# EXT_TMC222.net
KiCad netlist of a schematic drawn in EAGLE
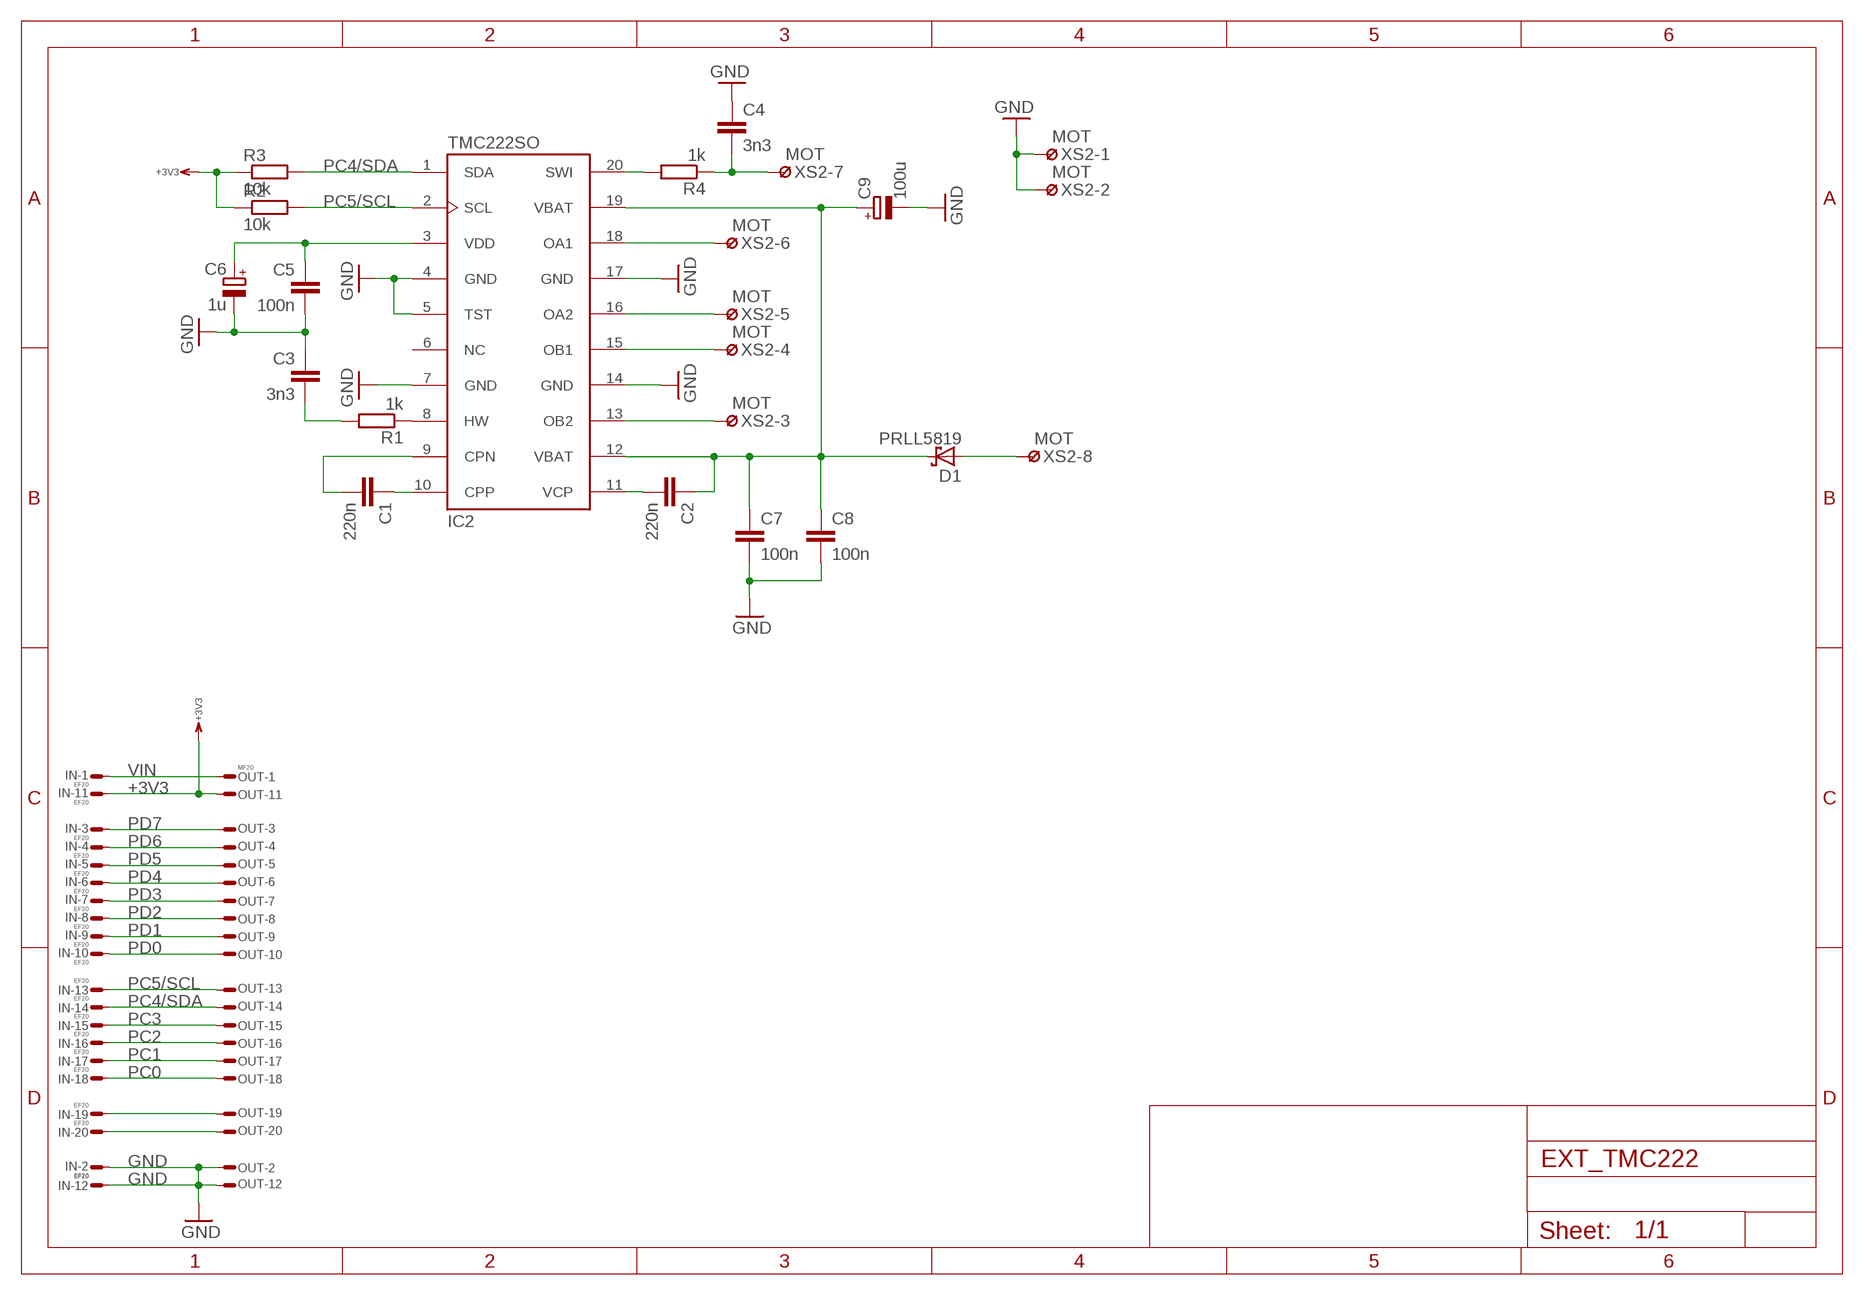
[diagram p0: schematic, sheet 1]

(export (version "E")
  (design (tool "Eeschema 10.0.6"))
  (components
    (comp (ref "C1")
      (value "220n")
      (footprint "eagle-import:1206")
      (libsource (lib "eagle-import") (part "C1206"))
    )
    (comp (ref "C2")
      (value "220n")
      (footprint "eagle-import:1206")
      (libsource (lib "eagle-import") (part "C1206"))
    )
    (comp (ref "C3")
      (value "3n3")
      (footprint "eagle-import:0603")
      (libsource (lib "eagle-import") (part "C0603"))
    )
    (comp (ref "C4")
      (value "3n3")
      (footprint "eagle-import:0603")
      (libsource (lib "eagle-import") (part "C0603"))
    )
    (comp (ref "C5")
      (value "100n")
      (footprint "eagle-import:0603")
      (libsource (lib "eagle-import") (part "C0603"))
    )
    (comp (ref "C6")
      (value "1u")
      (footprint "eagle-import:SMC_A")
      (libsource (lib "eagle-import") (part "C_POLSMCA"))
    )
    (comp (ref "C7")
      (value "100n")
      (footprint "eagle-import:1206")
      (libsource (lib "eagle-import") (part "C1206"))
    )
    (comp (ref "C8")
      (value "100n")
      (footprint "eagle-import:1206")
      (libsource (lib "eagle-import") (part "C1206"))
    )
    (comp (ref "C9")
      (value "100u")
      (footprint "eagle-import:E3,5-8")
      (libsource (lib "eagle-import") (part "C_POLE3.5-8"))
    )
    (comp (ref "D1")
      (value "PRLL5819")
      (footprint "eagle-import:SOD87")
      (libsource (lib "eagle-import") (part "D-SCHOTKY7"))
    )
    (comp (ref "IC2")
      (value "TMC222SO")
      (footprint "eagle-import:SOIC20")
      (libsource (lib "eagle-import") (part "TMC222SO"))
    )
    (comp (ref "IN")
      (value "EF20")
      (footprint "eagle-import:FE10-2WSS")
      (libsource (lib "eagle-import") (part "FE20ELSS"))
    )
    (comp (ref "OUT")
      (value "MF20")
      (footprint "eagle-import:ML20LS")
      (libsource (lib "eagle-import") (part "ML20?ELS"))
    )
    (comp (ref "R1")
      (value "1k")
      (footprint "eagle-import:0603")
      (libsource (lib "eagle-import") (part "R0603"))
    )
    (comp (ref "R2")
      (value "10k")
      (footprint "eagle-import:0603")
      (libsource (lib "eagle-import") (part "R0603"))
    )
    (comp (ref "R3")
      (value "10k")
      (footprint "eagle-import:0603")
      (libsource (lib "eagle-import") (part "R0603"))
    )
    (comp (ref "R4")
      (value "1k")
      (footprint "eagle-import:0603")
      (libsource (lib "eagle-import") (part "R0603"))
    )
    (comp (ref "XS2")
      (value "MOT")
      (footprint "eagle-import:1727078")
      (libsource (lib "eagle-import") (part "CON8-SS381"))
    )
  )
  (nets
    (net (code "1") (name "+3V3") (class "Default")
      (node (ref "IN") (pin "P$11") (pinfunction "S_P$11") (pintype "passive"))
      (node (ref "OUT") (pin "P$11") (pinfunction "S_P$11") (pintype "passive"))
      (node (ref "R2") (pin "1") (pinfunction "1_1") (pintype "passive"))
      (node (ref "R3") (pin "1") (pinfunction "1_1") (pintype "passive"))
    )
    (net (code "2") (name "/PC0") (class "Default")
      (node (ref "IN") (pin "P$18") (pinfunction "S_P$18") (pintype "passive"))
      (node (ref "OUT") (pin "P$18") (pinfunction "S_P$18") (pintype "passive"))
    )
    (net (code "3") (name "/PC1") (class "Default")
      (node (ref "IN") (pin "P$17") (pinfunction "S_P$17") (pintype "passive"))
      (node (ref "OUT") (pin "P$17") (pinfunction "S_P$17") (pintype "passive"))
    )
    (net (code "4") (name "/PC2") (class "Default")
      (node (ref "IN") (pin "P$16") (pinfunction "S_P$16") (pintype "passive"))
      (node (ref "OUT") (pin "P$16") (pinfunction "S_P$16") (pintype "passive"))
    )
    (net (code "5") (name "/PC3") (class "Default")
      (node (ref "IN") (pin "P$15") (pinfunction "S_P$15") (pintype "passive"))
      (node (ref "OUT") (pin "P$15") (pinfunction "S_P$15") (pintype "passive"))
    )
    (net (code "6") (name "/PC4{slash}SDA") (class "Default")
      (node (ref "IC2") (pin "1") (pinfunction "SDA_1") (pintype "bidirectional"))
      (node (ref "IN") (pin "P$14") (pinfunction "S_P$14") (pintype "passive"))
      (node (ref "OUT") (pin "P$14") (pinfunction "S_P$14") (pintype "passive"))
      (node (ref "R3") (pin "2") (pinfunction "2_2") (pintype "passive"))
    )
    (net (code "7") (name "/PC5{slash}SCL") (class "Default")
      (node (ref "IC2") (pin "2") (pinfunction "SCL_2") (pintype "bidirectional"))
      (node (ref "IN") (pin "P$13") (pinfunction "S_P$13") (pintype "passive"))
      (node (ref "OUT") (pin "P$13") (pinfunction "S_P$13") (pintype "passive"))
      (node (ref "R2") (pin "2") (pinfunction "2_2") (pintype "passive"))
    )
    (net (code "8") (name "/PD0") (class "Default")
      (node (ref "IN") (pin "P$10") (pinfunction "S_P$10") (pintype "passive"))
      (node (ref "OUT") (pin "P$10") (pinfunction "S_P$10") (pintype "passive"))
    )
    (net (code "9") (name "/PD1") (class "Default")
      (node (ref "IN") (pin "P$9") (pinfunction "S_P$9") (pintype "passive"))
      (node (ref "OUT") (pin "P$9") (pinfunction "S_P$9") (pintype "passive"))
    )
    (net (code "10") (name "/PD2") (class "Default")
      (node (ref "IN") (pin "P$8") (pinfunction "S_P$8") (pintype "passive"))
      (node (ref "OUT") (pin "P$8") (pinfunction "S_P$8") (pintype "passive"))
    )
    (net (code "11") (name "/PD3") (class "Default")
      (node (ref "IN") (pin "P$7") (pinfunction "S_P$7") (pintype "passive"))
      (node (ref "OUT") (pin "P$7") (pinfunction "S_P$7") (pintype "passive"))
    )
    (net (code "12") (name "/PD4") (class "Default")
      (node (ref "IN") (pin "P$6") (pinfunction "S_P$6") (pintype "passive"))
      (node (ref "OUT") (pin "P$6") (pinfunction "S_P$6") (pintype "passive"))
    )
    (net (code "13") (name "/PD5") (class "Default")
      (node (ref "IN") (pin "P$5") (pinfunction "S_P$5") (pintype "passive"))
      (node (ref "OUT") (pin "P$5") (pinfunction "S_P$5") (pintype "passive"))
    )
    (net (code "14") (name "/PD6") (class "Default")
      (node (ref "IN") (pin "P$4") (pinfunction "S_P$4") (pintype "passive"))
      (node (ref "OUT") (pin "P$4") (pinfunction "S_P$4") (pintype "passive"))
    )
    (net (code "15") (name "/PD7") (class "Default")
      (node (ref "IN") (pin "P$3") (pinfunction "S_P$3") (pintype "passive"))
      (node (ref "OUT") (pin "P$3") (pinfunction "S_P$3") (pintype "passive"))
    )
    (net (code "16") (name "/VIN") (class "Default")
      (node (ref "IN") (pin "P$1") (pinfunction "S_P$1") (pintype "passive"))
      (node (ref "OUT") (pin "P$1") (pinfunction "S_P$1") (pintype "passive"))
    )
    (net (code "17") (name "GND") (class "Default")
      (node (ref "C3") (pin "1") (pinfunction "1_1") (pintype "passive"))
      (node (ref "C4") (pin "1") (pinfunction "1_1") (pintype "passive"))
      (node (ref "C5") (pin "2") (pinfunction "2_2") (pintype "passive"))
      (node (ref "C6") (pin "-") (pinfunction "-_-") (pintype "passive"))
      (node (ref "C7") (pin "2") (pinfunction "2_2") (pintype "passive"))
      (node (ref "C8") (pin "2") (pinfunction "2_2") (pintype "passive"))
      (node (ref "C9") (pin "-") (pinfunction "-_-") (pintype "passive"))
      (node (ref "IC2") (pin "14") (pinfunction "GND_14") (pintype "bidirectional"))
      (node (ref "IC2") (pin "17") (pinfunction "GND_17") (pintype "bidirectional"))
      (node (ref "IC2") (pin "4") (pinfunction "GND_4") (pintype "bidirectional"))
      (node (ref "IC2") (pin "5") (pinfunction "TST_5") (pintype "input"))
      (node (ref "IC2") (pin "7") (pinfunction "GND_7") (pintype "bidirectional"))
      (node (ref "IN") (pin "P$12") (pinfunction "S_P$12") (pintype "passive"))
      (node (ref "IN") (pin "P$2") (pinfunction "S_P$2") (pintype "passive"))
      (node (ref "OUT") (pin "P$12") (pinfunction "S_P$12") (pintype "passive"))
      (node (ref "OUT") (pin "P$2") (pinfunction "S_P$2") (pintype "passive"))
      (node (ref "XS2") (pin "P$1") (pinfunction "K_P$1") (pintype "passive"))
      (node (ref "XS2") (pin "P$2") (pinfunction "K_P$2") (pintype "passive"))
    )
    (net (code "18") (name "Net-(C2-Pad1)") (class "Default")
      (node (ref "C2") (pin "1") (pinfunction "1_1") (pintype "passive"))
      (node (ref "C7") (pin "1") (pinfunction "1_1") (pintype "passive"))
      (node (ref "C8") (pin "1") (pinfunction "1_1") (pintype "passive"))
      (node (ref "C9") (pin "+") (pinfunction "+_+") (pintype "passive"))
      (node (ref "D1") (pin "C") (pinfunction "C_C") (pintype "passive"))
      (node (ref "IC2") (pin "12") (pinfunction "VBAT_12") (pintype "input"))
      (node (ref "IC2") (pin "19") (pinfunction "VBAT_19") (pintype "input"))
    )
    (net (code "19") (name "Net-(C3-Pad2)") (class "Default")
      (node (ref "C3") (pin "2") (pinfunction "2_2") (pintype "passive"))
      (node (ref "R1") (pin "2") (pinfunction "2_2") (pintype "passive"))
    )
    (net (code "20") (name "Net-(IC2-CPN)") (class "Default")
      (node (ref "C1") (pin "2") (pinfunction "2_2") (pintype "passive"))
      (node (ref "IC2") (pin "9") (pinfunction "CPN_9") (pintype "bidirectional"))
    )
    (net (code "21") (name "Net-(IC2-CPP)") (class "Default")
      (node (ref "C1") (pin "1") (pinfunction "1_1") (pintype "passive"))
      (node (ref "IC2") (pin "10") (pinfunction "CPP_10") (pintype "bidirectional"))
    )
    (net (code "22") (name "Net-(IC2-HW)") (class "Default")
      (node (ref "IC2") (pin "8") (pinfunction "HW_8") (pintype "input"))
      (node (ref "R1") (pin "1") (pinfunction "1_1") (pintype "passive"))
    )
    (net (code "23") (name "Net-(IC2-OA1)") (class "Default")
      (node (ref "IC2") (pin "18") (pinfunction "OA1_18") (pintype "bidirectional"))
      (node (ref "XS2") (pin "P$6") (pinfunction "K_P$6") (pintype "passive"))
    )
    (net (code "24") (name "Net-(IC2-OA2)") (class "Default")
      (node (ref "IC2") (pin "16") (pinfunction "OA2_16") (pintype "bidirectional"))
      (node (ref "XS2") (pin "P$5") (pinfunction "K_P$5") (pintype "passive"))
    )
    (net (code "25") (name "Net-(IC2-OB1)") (class "Default")
      (node (ref "IC2") (pin "15") (pinfunction "OB1_15") (pintype "bidirectional"))
      (node (ref "XS2") (pin "P$4") (pinfunction "K_P$4") (pintype "passive"))
    )
    (net (code "26") (name "Net-(IC2-OB2)") (class "Default")
      (node (ref "IC2") (pin "13") (pinfunction "OB2_13") (pintype "bidirectional"))
      (node (ref "XS2") (pin "P$3") (pinfunction "K_P$3") (pintype "passive"))
    )
    (net (code "27") (name "Net-(IC2-SWI)") (class "Default")
      (node (ref "IC2") (pin "20") (pinfunction "SWI_20") (pintype "input"))
      (node (ref "R4") (pin "2") (pinfunction "2_2") (pintype "passive"))
    )
    (net (code "28") (name "Net-(IC2-VCP)") (class "Default")
      (node (ref "C2") (pin "2") (pinfunction "2_2") (pintype "passive"))
      (node (ref "IC2") (pin "11") (pinfunction "VCP_11") (pintype "bidirectional"))
    )
    (net (code "29") (name "Net-(IC2-VDD)") (class "Default")
      (node (ref "C5") (pin "1") (pinfunction "1_1") (pintype "passive"))
      (node (ref "C6") (pin "+") (pinfunction "+_+") (pintype "passive"))
      (node (ref "IC2") (pin "3") (pinfunction "VDD_3") (pintype "bidirectional"))
    )
    (net (code "30") (name "Net-(INK-S)") (class "Default")
      (node (ref "IN") (pin "P$19") (pinfunction "S_P$19") (pintype "passive"))
      (node (ref "OUT") (pin "P$19") (pinfunction "S_P$19") (pintype "passive"))
    )
    (net (code "31") (name "Net-(INM-S)") (class "Default")
      (node (ref "IN") (pin "P$20") (pinfunction "S_P$20") (pintype "passive"))
      (node (ref "OUT") (pin "P$20") (pinfunction "S_P$20") (pintype "passive"))
    )
    (net (code "32") (name "Net-(XS2G-K)") (class "Default")
      (node (ref "C4") (pin "2") (pinfunction "2_2") (pintype "passive"))
      (node (ref "R4") (pin "1") (pinfunction "1_1") (pintype "passive"))
      (node (ref "XS2") (pin "P$7") (pinfunction "K_P$7") (pintype "passive"))
    )
    (net (code "33") (name "Net-(XS2H-K)") (class "Default")
      (node (ref "D1") (pin "A") (pinfunction "A_A") (pintype "passive"))
      (node (ref "XS2") (pin "P$8") (pinfunction "K_P$8") (pintype "passive"))
    )
    (net (code "34") (name "unconnected-(IC2-NC-Pad6)") (class "Default")
      (node (ref "IC2") (pin "6") (pinfunction "NC_6") (pintype "no_connect"))
    )
  )
)
